# DropScreenMay2016DriversBoard.net
KiCad netlist of a schematic drawn in EAGLE
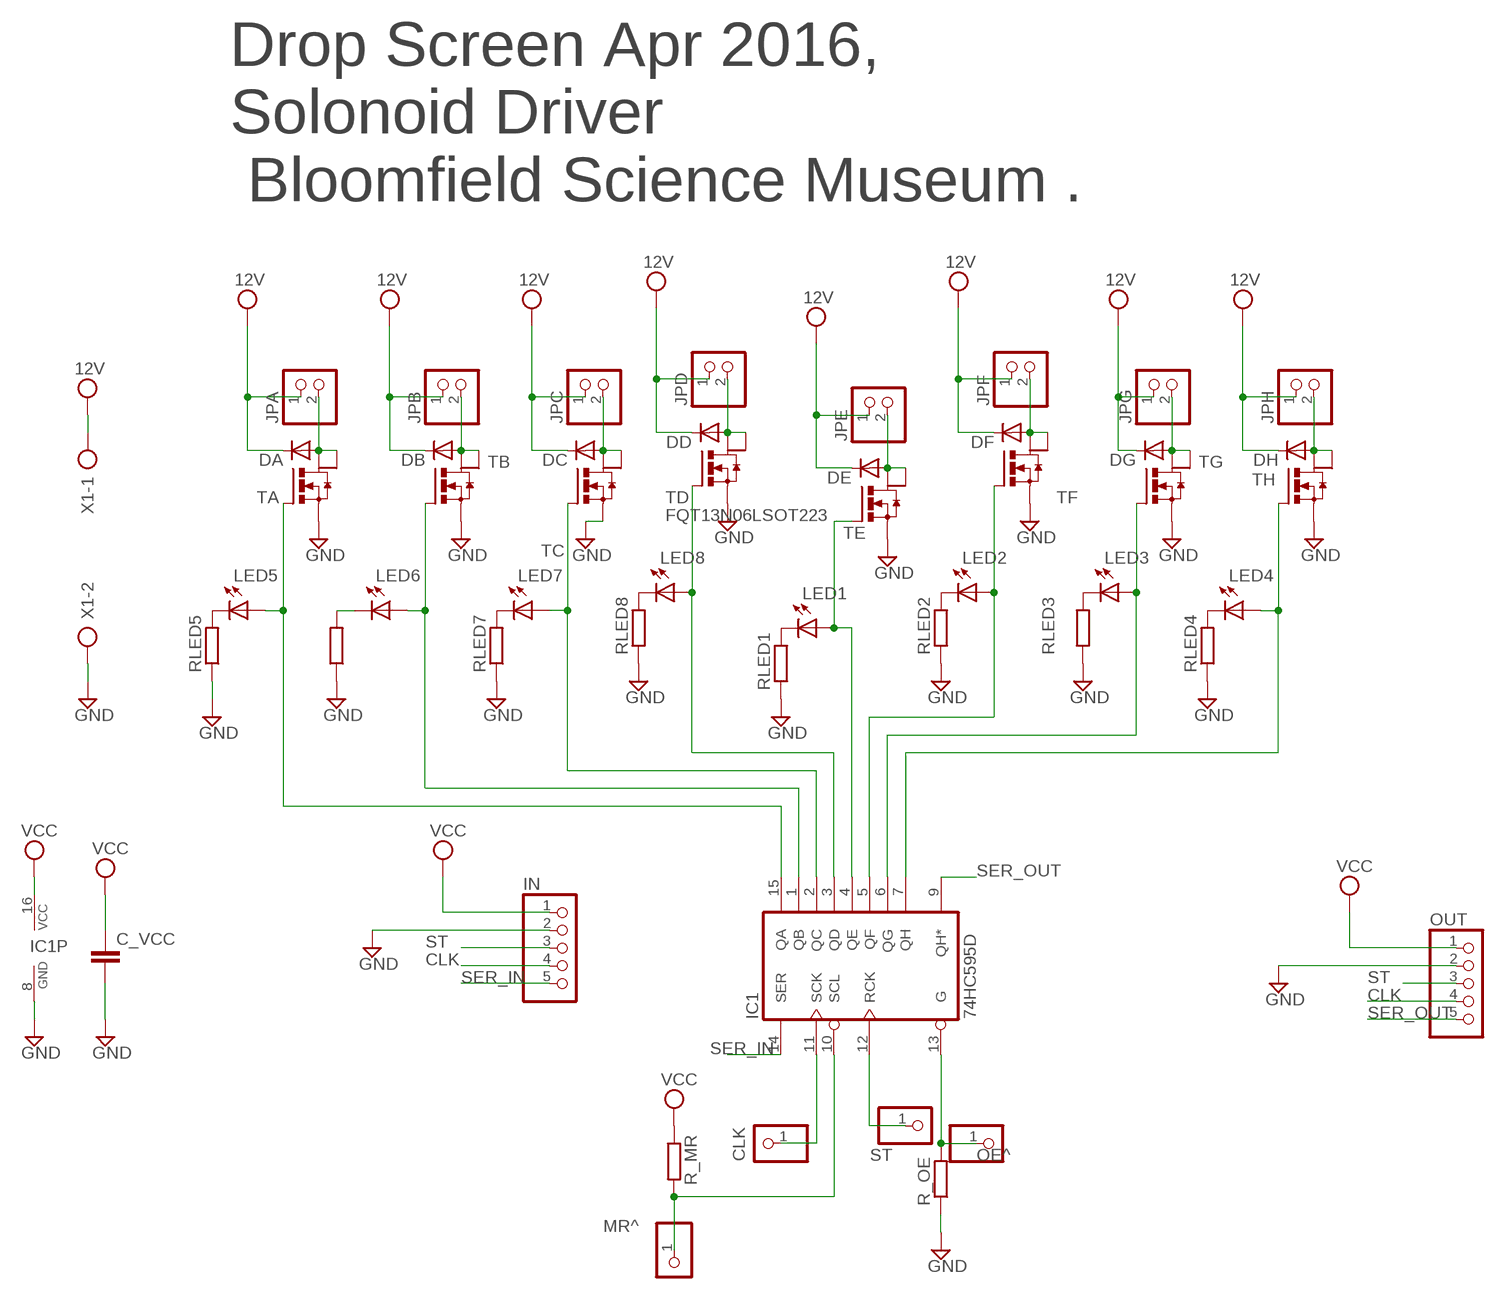
[diagram p0: schematic, sheet 1]

(export (version "E")
  (design (tool "Eeschema 10.0.6"))
  (components
    (comp (ref "CLK")
      (value "PINHD-1X1")
      (footprint "eagle-import:1X01")
      (libsource (lib "eagle-import") (part "PINHD-1X1"))
    )
    (comp (ref "CLK1")
      (value "PINHD-1X1")
      (footprint "eagle-import:1X01")
      (libsource (lib "eagle-import") (part "PINHD-1X1"))
    )
    (comp (ref "C_VCC")
      (value "C-EUC0805")
      (footprint "eagle-import:C0805")
      (libsource (lib "eagle-import") (part "C-EUC0805"))
    )
    (comp (ref "DA")
      (value "1N4004V")
      (footprint "eagle-import:DO41-25")
      (libsource (lib "eagle-import") (part "1N4004V"))
    )
    (comp (ref "DB")
      (value "1N4004V")
      (footprint "eagle-import:DO41-25")
      (libsource (lib "eagle-import") (part "1N4004V"))
    )
    (comp (ref "DC")
      (value "1N4004V")
      (footprint "eagle-import:DO41-25")
      (libsource (lib "eagle-import") (part "1N4004V"))
    )
    (comp (ref "DD")
      (value "1N4004V")
      (footprint "eagle-import:DO41-25")
      (libsource (lib "eagle-import") (part "1N4004V"))
    )
    (comp (ref "DE")
      (value "1N4004V")
      (footprint "eagle-import:DO41-25")
      (libsource (lib "eagle-import") (part "1N4004V"))
    )
    (comp (ref "DF")
      (value "1N4004V")
      (footprint "eagle-import:DO41-25")
      (libsource (lib "eagle-import") (part "1N4004V"))
    )
    (comp (ref "DG")
      (value "1N4004V")
      (footprint "eagle-import:DO41-25")
      (libsource (lib "eagle-import") (part "1N4004V"))
    )
    (comp (ref "DH")
      (value "1N4004V")
      (footprint "eagle-import:DO41-25")
      (libsource (lib "eagle-import") (part "1N4004V"))
    )
    (comp (ref "IC1")
      (value "74HC595D")
      (footprint "eagle-import:SO16")
      (libsource (lib "eagle-import") (part "74595DHC"))
    )
    (comp (ref "IN")
      (value "PIN_HEAD_1X5_MARKEDSMAOLPAD")
      (footprint "eagle-import:1X5_MARKED_SMALL_PADS")
      (libsource (lib "eagle-import") (part "PIN_HEAD_1X5_MARKEDSMAOLPAD"))
    )
    (comp (ref "JPA")
      (value "PINHD-1X2SQ&RND")
      (footprint "eagle-import:1X02_SQ&ROUND")
      (libsource (lib "eagle-import") (part "PINHD-1X2SQ&RND"))
    )
    (comp (ref "JPB")
      (value "PINHD-1X2SQ&RND")
      (footprint "eagle-import:1X02_SQ&ROUND")
      (libsource (lib "eagle-import") (part "PINHD-1X2SQ&RND"))
    )
    (comp (ref "JPC")
      (value "PINHD-1X2SQ&RND")
      (footprint "eagle-import:1X02_SQ&ROUND")
      (libsource (lib "eagle-import") (part "PINHD-1X2SQ&RND"))
    )
    (comp (ref "JPD")
      (value "PINHD-1X2SQ&RND")
      (footprint "eagle-import:1X02_SQ&ROUND")
      (libsource (lib "eagle-import") (part "PINHD-1X2SQ&RND"))
    )
    (comp (ref "JPE")
      (value "PINHD-1X2SQ&RND")
      (footprint "eagle-import:1X02_SQ&ROUND")
      (libsource (lib "eagle-import") (part "PINHD-1X2SQ&RND"))
    )
    (comp (ref "JPF")
      (value "PINHD-1X2SQ&RND")
      (footprint "eagle-import:1X02_SQ&ROUND")
      (libsource (lib "eagle-import") (part "PINHD-1X2SQ&RND"))
    )
    (comp (ref "JPG")
      (value "PINHD-1X2SQ&RND")
      (footprint "eagle-import:1X02_SQ&ROUND")
      (libsource (lib "eagle-import") (part "PINHD-1X2SQ&RND"))
    )
    (comp (ref "JPH")
      (value "PINHD-1X2SQ&RND")
      (footprint "eagle-import:1X02_SQ&ROUND")
      (libsource (lib "eagle-import") (part "PINHD-1X2SQ&RND"))
    )
    (comp (ref "LED1")
      (value "LEDCHIPLED_0805")
      (footprint "eagle-import:CHIPLED_0805")
      (libsource (lib "eagle-import") (part "LEDCHIPLED_0805"))
    )
    (comp (ref "LED2")
      (value "LEDCHIPLED_0805")
      (footprint "eagle-import:CHIPLED_0805")
      (libsource (lib "eagle-import") (part "LEDCHIPLED_0805"))
    )
    (comp (ref "LED3")
      (value "LEDCHIPLED_0805")
      (footprint "eagle-import:CHIPLED_0805")
      (libsource (lib "eagle-import") (part "LEDCHIPLED_0805"))
    )
    (comp (ref "LED4")
      (value "LEDCHIPLED_0805")
      (footprint "eagle-import:CHIPLED_0805")
      (libsource (lib "eagle-import") (part "LEDCHIPLED_0805"))
    )
    (comp (ref "LED5")
      (value "LEDCHIPLED_0805")
      (footprint "eagle-import:CHIPLED_0805")
      (libsource (lib "eagle-import") (part "LEDCHIPLED_0805"))
    )
    (comp (ref "LED6")
      (value "LEDCHIPLED_0805")
      (footprint "eagle-import:CHIPLED_0805")
      (libsource (lib "eagle-import") (part "LEDCHIPLED_0805"))
    )
    (comp (ref "LED7")
      (value "LEDCHIPLED_0805")
      (footprint "eagle-import:CHIPLED_0805")
      (libsource (lib "eagle-import") (part "LEDCHIPLED_0805"))
    )
    (comp (ref "LED8")
      (value "LEDCHIPLED_0805")
      (footprint "eagle-import:CHIPLED_0805")
      (libsource (lib "eagle-import") (part "LEDCHIPLED_0805"))
    )
    (comp (ref "OE^")
      (value "CLR")
      (footprint "eagle-import:1X01")
      (libsource (lib "eagle-import") (part "PINHD-1X1"))
    )
    (comp (ref "OUT")
      (value "PIN_HEAD_1X5_MARKEDSMAOLPAD")
      (footprint "eagle-import:1X5_MARKED_SMALL_PADS")
      (libsource (lib "eagle-import") (part "PIN_HEAD_1X5_MARKEDSMAOLPAD"))
    )
    (comp (ref "RLED1")
      (value "R-EU_R0603")
      (footprint "eagle-import:R0603")
      (libsource (lib "eagle-import") (part "R-EU_R0603"))
    )
    (comp (ref "RLED2")
      (value "R-EU_R0603")
      (footprint "eagle-import:R0603")
      (libsource (lib "eagle-import") (part "R-EU_R0603"))
    )
    (comp (ref "RLED3")
      (value "R-EU_R0603")
      (footprint "eagle-import:R0603")
      (libsource (lib "eagle-import") (part "R-EU_R0603"))
    )
    (comp (ref "RLED4")
      (value "R-EU_R0603")
      (footprint "eagle-import:R0603")
      (libsource (lib "eagle-import") (part "R-EU_R0603"))
    )
    (comp (ref "RLED5")
      (value "R-EU_R0603")
      (footprint "eagle-import:R0603")
      (libsource (lib "eagle-import") (part "R-EU_R0603"))
    )
    (comp (ref "RLED6")
      (value "R-EU_R0603")
      (footprint "eagle-import:R0603")
      (libsource (lib "eagle-import") (part "R-EU_R0603"))
    )
    (comp (ref "RLED7")
      (value "R-EU_R0603")
      (footprint "eagle-import:R0603")
      (libsource (lib "eagle-import") (part "R-EU_R0603"))
    )
    (comp (ref "RLED8")
      (value "R-EU_R0603")
      (footprint "eagle-import:R0603")
      (libsource (lib "eagle-import") (part "R-EU_R0603"))
    )
    (comp (ref "R_MR")
      (value "R-EU_R0603")
      (footprint "eagle-import:R0603")
      (libsource (lib "eagle-import") (part "R-EU_R0603"))
    )
    (comp (ref "R_OE")
      (value "R-EU_R0603")
      (footprint "eagle-import:R0603")
      (libsource (lib "eagle-import") (part "R-EU_R0603"))
    )
    (comp (ref "ST")
      (value "ST")
      (footprint "eagle-import:1X01")
      (libsource (lib "eagle-import") (part "PINHD-1X1"))
    )
    (comp (ref "TA")
      (value "FQT13N06LSOT223")
      (footprint "eagle-import:SOT223")
      (libsource (lib "eagle-import") (part "FQT13N06LSOT223"))
    )
    (comp (ref "TB")
      (value "FQT13N06LSOT223")
      (footprint "eagle-import:SOT223")
      (libsource (lib "eagle-import") (part "FQT13N06LSOT223"))
    )
    (comp (ref "TC")
      (value "FQT13N06LSOT223")
      (footprint "eagle-import:SOT223")
      (libsource (lib "eagle-import") (part "FQT13N06LSOT223"))
    )
    (comp (ref "TD")
      (value "FQT13N06LSOT223")
      (footprint "eagle-import:SOT223")
      (libsource (lib "eagle-import") (part "FQT13N06LSOT223"))
    )
    (comp (ref "TE")
      (value "FQT13N06LSOT223")
      (footprint "eagle-import:SOT223")
      (libsource (lib "eagle-import") (part "FQT13N06LSOT223"))
    )
    (comp (ref "TF")
      (value "FQT13N06LSOT223")
      (footprint "eagle-import:SOT223")
      (libsource (lib "eagle-import") (part "FQT13N06LSOT223"))
    )
    (comp (ref "TG")
      (value "FQT13N06LSOT223")
      (footprint "eagle-import:SOT223")
      (libsource (lib "eagle-import") (part "FQT13N06LSOT223"))
    )
    (comp (ref "TH")
      (value "FQT13N06LSOT223")
      (footprint "eagle-import:SOT223")
      (libsource (lib "eagle-import") (part "FQT13N06LSOT223"))
    )
    (comp (ref "X1")
      (value "AK300/2")
      (footprint "eagle-import:AK300_2")
      (libsource (lib "eagle-import") (part "AK300/2"))
    )
  )
  (nets
    (net (code "1") (name "/CLK") (class "Default")
      (node (ref "CLK") (pin "1") (pinfunction "1_1") (pintype "passive"))
      (node (ref "IC1") (pin "11") (pinfunction "SCK_11") (pintype "input"))
      (node (ref "IN") (pin "4") (pinfunction "4_4") (pintype "passive"))
      (node (ref "OUT") (pin "4") (pinfunction "4_4") (pintype "passive"))
    )
    (net (code "2") (name "/MR^") (class "Default")
      (node (ref "CLK1") (pin "1") (pinfunction "1_1") (pintype "passive"))
      (node (ref "IC1") (pin "10") (pinfunction "SCL_10") (pintype "input"))
      (node (ref "R_MR") (pin "2") (pinfunction "2_2") (pintype "passive"))
    )
    (net (code "3") (name "/OE^") (class "Default")
      (node (ref "IC1") (pin "13") (pinfunction "G_13") (pintype "input"))
      (node (ref "OE^") (pin "1") (pinfunction "1_1") (pintype "passive"))
      (node (ref "R_OE") (pin "2") (pinfunction "2_2") (pintype "passive"))
    )
    (net (code "4") (name "/SER_IN") (class "Default")
      (node (ref "IC1") (pin "14") (pinfunction "SER_14") (pintype "input"))
      (node (ref "IN") (pin "5") (pinfunction "5_5") (pintype "passive"))
    )
    (net (code "5") (name "/SER_OUT") (class "Default")
      (node (ref "IC1") (pin "9") (pinfunction "QH*_9") (pintype "tri_state"))
      (node (ref "OUT") (pin "5") (pinfunction "5_5") (pintype "passive"))
    )
    (net (code "6") (name "/ST") (class "Default")
      (node (ref "IC1") (pin "12") (pinfunction "RCK_12") (pintype "input"))
      (node (ref "IN") (pin "3") (pinfunction "3_3") (pintype "passive"))
      (node (ref "OUT") (pin "3") (pinfunction "3_3") (pintype "passive"))
      (node (ref "ST") (pin "1") (pinfunction "1_1") (pintype "passive"))
    )
    (net (code "7") (name "12V") (class "Default")
      (node (ref "DA") (pin "C") (pinfunction "C_C") (pintype "passive"))
      (node (ref "DB") (pin "C") (pinfunction "C_C") (pintype "passive"))
      (node (ref "DC") (pin "C") (pinfunction "C_C") (pintype "passive"))
      (node (ref "DD") (pin "C") (pinfunction "C_C") (pintype "passive"))
      (node (ref "DE") (pin "C") (pinfunction "C_C") (pintype "passive"))
      (node (ref "DF") (pin "C") (pinfunction "C_C") (pintype "passive"))
      (node (ref "DG") (pin "C") (pinfunction "C_C") (pintype "passive"))
      (node (ref "DH") (pin "C") (pinfunction "C_C") (pintype "passive"))
      (node (ref "JPA") (pin "1") (pinfunction "1_1") (pintype "passive"))
      (node (ref "JPB") (pin "1") (pinfunction "1_1") (pintype "passive"))
      (node (ref "JPC") (pin "1") (pinfunction "1_1") (pintype "passive"))
      (node (ref "JPD") (pin "1") (pinfunction "1_1") (pintype "passive"))
      (node (ref "JPE") (pin "1") (pinfunction "1_1") (pintype "passive"))
      (node (ref "JPF") (pin "1") (pinfunction "1_1") (pintype "passive"))
      (node (ref "JPG") (pin "1") (pinfunction "1_1") (pintype "passive"))
      (node (ref "JPH") (pin "1") (pinfunction "1_1") (pintype "passive"))
      (node (ref "X1") (pin "1") (pinfunction "KL_1") (pintype "passive"))
    )
    (net (code "8") (name "GND") (class "Default")
      (node (ref "C_VCC") (pin "2") (pinfunction "2_2") (pintype "passive"))
      (node (ref "IC1") (pin "8") (pinfunction "GND_8") (pintype "power_in"))
      (node (ref "IN") (pin "2") (pinfunction "2_2") (pintype "passive"))
      (node (ref "OUT") (pin "2") (pinfunction "2_2") (pintype "passive"))
      (node (ref "RLED1") (pin "1") (pinfunction "1_1") (pintype "passive"))
      (node (ref "RLED2") (pin "1") (pinfunction "1_1") (pintype "passive"))
      (node (ref "RLED3") (pin "1") (pinfunction "1_1") (pintype "passive"))
      (node (ref "RLED4") (pin "1") (pinfunction "1_1") (pintype "passive"))
      (node (ref "RLED5") (pin "1") (pinfunction "1_1") (pintype "passive"))
      (node (ref "RLED6") (pin "1") (pinfunction "1_1") (pintype "passive"))
      (node (ref "RLED7") (pin "1") (pinfunction "1_1") (pintype "passive"))
      (node (ref "RLED8") (pin "1") (pinfunction "1_1") (pintype "passive"))
      (node (ref "R_OE") (pin "1") (pinfunction "1_1") (pintype "passive"))
      (node (ref "TA") (pin "3") (pinfunction "S_3") (pintype "passive"))
      (node (ref "TB") (pin "3") (pinfunction "S_3") (pintype "passive"))
      (node (ref "TC") (pin "3") (pinfunction "S_3") (pintype "passive"))
      (node (ref "TD") (pin "3") (pinfunction "S_3") (pintype "passive"))
      (node (ref "TE") (pin "3") (pinfunction "S_3") (pintype "passive"))
      (node (ref "TF") (pin "3") (pinfunction "S_3") (pintype "passive"))
      (node (ref "TG") (pin "3") (pinfunction "S_3") (pintype "passive"))
      (node (ref "TH") (pin "3") (pinfunction "S_3") (pintype "passive"))
      (node (ref "X1") (pin "2") (pinfunction "KL_2") (pintype "passive"))
    )
    (net (code "9") (name "Net-(IC1A-QA)") (class "Default")
      (node (ref "IC1") (pin "15") (pinfunction "QA_15") (pintype "tri_state"))
      (node (ref "LED5") (pin "A") (pinfunction "A_A") (pintype "passive"))
      (node (ref "TA") (pin "1") (pinfunction "G_1") (pintype "passive"))
    )
    (net (code "10") (name "Net-(IC1A-QB)") (class "Default")
      (node (ref "IC1") (pin "1") (pinfunction "QB_1") (pintype "tri_state"))
      (node (ref "LED6") (pin "A") (pinfunction "A_A") (pintype "passive"))
      (node (ref "TB") (pin "1") (pinfunction "G_1") (pintype "passive"))
    )
    (net (code "11") (name "Net-(IC1A-QC)") (class "Default")
      (node (ref "IC1") (pin "2") (pinfunction "QC_2") (pintype "tri_state"))
      (node (ref "LED7") (pin "A") (pinfunction "A_A") (pintype "passive"))
      (node (ref "TC") (pin "1") (pinfunction "G_1") (pintype "passive"))
    )
    (net (code "12") (name "Net-(IC1A-QD)") (class "Default")
      (node (ref "IC1") (pin "3") (pinfunction "QD_3") (pintype "tri_state"))
      (node (ref "LED8") (pin "A") (pinfunction "A_A") (pintype "passive"))
      (node (ref "TD") (pin "1") (pinfunction "G_1") (pintype "passive"))
    )
    (net (code "13") (name "Net-(IC1A-QE)") (class "Default")
      (node (ref "IC1") (pin "4") (pinfunction "QE_4") (pintype "tri_state"))
      (node (ref "LED1") (pin "A") (pinfunction "A_A") (pintype "passive"))
      (node (ref "TE") (pin "1") (pinfunction "G_1") (pintype "passive"))
    )
    (net (code "14") (name "Net-(IC1A-QF)") (class "Default")
      (node (ref "IC1") (pin "5") (pinfunction "QF_5") (pintype "tri_state"))
      (node (ref "LED2") (pin "A") (pinfunction "A_A") (pintype "passive"))
      (node (ref "TF") (pin "1") (pinfunction "G_1") (pintype "passive"))
    )
    (net (code "15") (name "Net-(IC1A-QG)") (class "Default")
      (node (ref "IC1") (pin "6") (pinfunction "QG_6") (pintype "tri_state"))
      (node (ref "LED3") (pin "A") (pinfunction "A_A") (pintype "passive"))
      (node (ref "TG") (pin "1") (pinfunction "G_1") (pintype "passive"))
    )
    (net (code "16") (name "Net-(IC1A-QH)") (class "Default")
      (node (ref "IC1") (pin "7") (pinfunction "QH_7") (pintype "tri_state"))
      (node (ref "LED4") (pin "A") (pinfunction "A_A") (pintype "passive"))
      (node (ref "TH") (pin "1") (pinfunction "G_1") (pintype "passive"))
    )
    (net (code "17") (name "Net-(LED1-PadC)") (class "Default")
      (node (ref "LED1") (pin "C") (pinfunction "C_C") (pintype "passive"))
      (node (ref "RLED1") (pin "2") (pinfunction "2_2") (pintype "passive"))
    )
    (net (code "18") (name "Net-(LED2-PadC)") (class "Default")
      (node (ref "LED2") (pin "C") (pinfunction "C_C") (pintype "passive"))
      (node (ref "RLED2") (pin "2") (pinfunction "2_2") (pintype "passive"))
    )
    (net (code "19") (name "Net-(LED3-PadC)") (class "Default")
      (node (ref "LED3") (pin "C") (pinfunction "C_C") (pintype "passive"))
      (node (ref "RLED3") (pin "2") (pinfunction "2_2") (pintype "passive"))
    )
    (net (code "20") (name "Net-(LED4-PadC)") (class "Default")
      (node (ref "LED4") (pin "C") (pinfunction "C_C") (pintype "passive"))
      (node (ref "RLED4") (pin "2") (pinfunction "2_2") (pintype "passive"))
    )
    (net (code "21") (name "Net-(LED5-PadC)") (class "Default")
      (node (ref "LED5") (pin "C") (pinfunction "C_C") (pintype "passive"))
      (node (ref "RLED5") (pin "2") (pinfunction "2_2") (pintype "passive"))
    )
    (net (code "22") (name "Net-(LED6-PadC)") (class "Default")
      (node (ref "LED6") (pin "C") (pinfunction "C_C") (pintype "passive"))
      (node (ref "RLED6") (pin "2") (pinfunction "2_2") (pintype "passive"))
    )
    (net (code "23") (name "Net-(LED7-PadC)") (class "Default")
      (node (ref "LED7") (pin "C") (pinfunction "C_C") (pintype "passive"))
      (node (ref "RLED7") (pin "2") (pinfunction "2_2") (pintype "passive"))
    )
    (net (code "24") (name "Net-(LED8-PadC)") (class "Default")
      (node (ref "LED8") (pin "C") (pinfunction "C_C") (pintype "passive"))
      (node (ref "RLED8") (pin "2") (pinfunction "2_2") (pintype "passive"))
    )
    (net (code "25") (name "Net-(TA-D)") (class "Default")
      (node (ref "DA") (pin "A") (pinfunction "A_A") (pintype "passive"))
      (node (ref "JPA") (pin "2") (pinfunction "2_2") (pintype "passive"))
      (node (ref "TA") (pin "2") (pinfunction "D_2") (pintype "passive"))
      (node (ref "TA") (pin "4") (pinfunction "D1_4") (pintype "passive"))
    )
    (net (code "26") (name "Net-(TB-D)") (class "Default")
      (node (ref "DB") (pin "A") (pinfunction "A_A") (pintype "passive"))
      (node (ref "JPB") (pin "2") (pinfunction "2_2") (pintype "passive"))
      (node (ref "TB") (pin "2") (pinfunction "D_2") (pintype "passive"))
      (node (ref "TB") (pin "4") (pinfunction "D1_4") (pintype "passive"))
    )
    (net (code "27") (name "Net-(TC-D)") (class "Default")
      (node (ref "DC") (pin "A") (pinfunction "A_A") (pintype "passive"))
      (node (ref "JPC") (pin "2") (pinfunction "2_2") (pintype "passive"))
      (node (ref "TC") (pin "2") (pinfunction "D_2") (pintype "passive"))
      (node (ref "TC") (pin "4") (pinfunction "D1_4") (pintype "passive"))
    )
    (net (code "28") (name "Net-(TD-D)") (class "Default")
      (node (ref "DD") (pin "A") (pinfunction "A_A") (pintype "passive"))
      (node (ref "JPD") (pin "2") (pinfunction "2_2") (pintype "passive"))
      (node (ref "TD") (pin "2") (pinfunction "D_2") (pintype "passive"))
      (node (ref "TD") (pin "4") (pinfunction "D1_4") (pintype "passive"))
    )
    (net (code "29") (name "Net-(TE-D)") (class "Default")
      (node (ref "DE") (pin "A") (pinfunction "A_A") (pintype "passive"))
      (node (ref "JPE") (pin "2") (pinfunction "2_2") (pintype "passive"))
      (node (ref "TE") (pin "2") (pinfunction "D_2") (pintype "passive"))
      (node (ref "TE") (pin "4") (pinfunction "D1_4") (pintype "passive"))
    )
    (net (code "30") (name "Net-(TF-D)") (class "Default")
      (node (ref "DF") (pin "A") (pinfunction "A_A") (pintype "passive"))
      (node (ref "JPF") (pin "2") (pinfunction "2_2") (pintype "passive"))
      (node (ref "TF") (pin "2") (pinfunction "D_2") (pintype "passive"))
      (node (ref "TF") (pin "4") (pinfunction "D1_4") (pintype "passive"))
    )
    (net (code "31") (name "Net-(TG-D)") (class "Default")
      (node (ref "DG") (pin "A") (pinfunction "A_A") (pintype "passive"))
      (node (ref "JPG") (pin "2") (pinfunction "2_2") (pintype "passive"))
      (node (ref "TG") (pin "2") (pinfunction "D_2") (pintype "passive"))
      (node (ref "TG") (pin "4") (pinfunction "D1_4") (pintype "passive"))
    )
    (net (code "32") (name "Net-(TH-D)") (class "Default")
      (node (ref "DH") (pin "A") (pinfunction "A_A") (pintype "passive"))
      (node (ref "JPH") (pin "2") (pinfunction "2_2") (pintype "passive"))
      (node (ref "TH") (pin "2") (pinfunction "D_2") (pintype "passive"))
      (node (ref "TH") (pin "4") (pinfunction "D1_4") (pintype "passive"))
    )
    (net (code "33") (name "VCC") (class "Default")
      (node (ref "C_VCC") (pin "1") (pinfunction "1_1") (pintype "passive"))
      (node (ref "IC1") (pin "16") (pinfunction "VCC_16") (pintype "power_in"))
      (node (ref "IN") (pin "1") (pinfunction "1_1") (pintype "passive"))
      (node (ref "OUT") (pin "1") (pinfunction "1_1") (pintype "passive"))
      (node (ref "R_MR") (pin "1") (pinfunction "1_1") (pintype "passive"))
    )
  )
)
